# 1-Schematic_Power-vibrator_module.net
KiCad netlist of a schematic drawn in EasyEDA
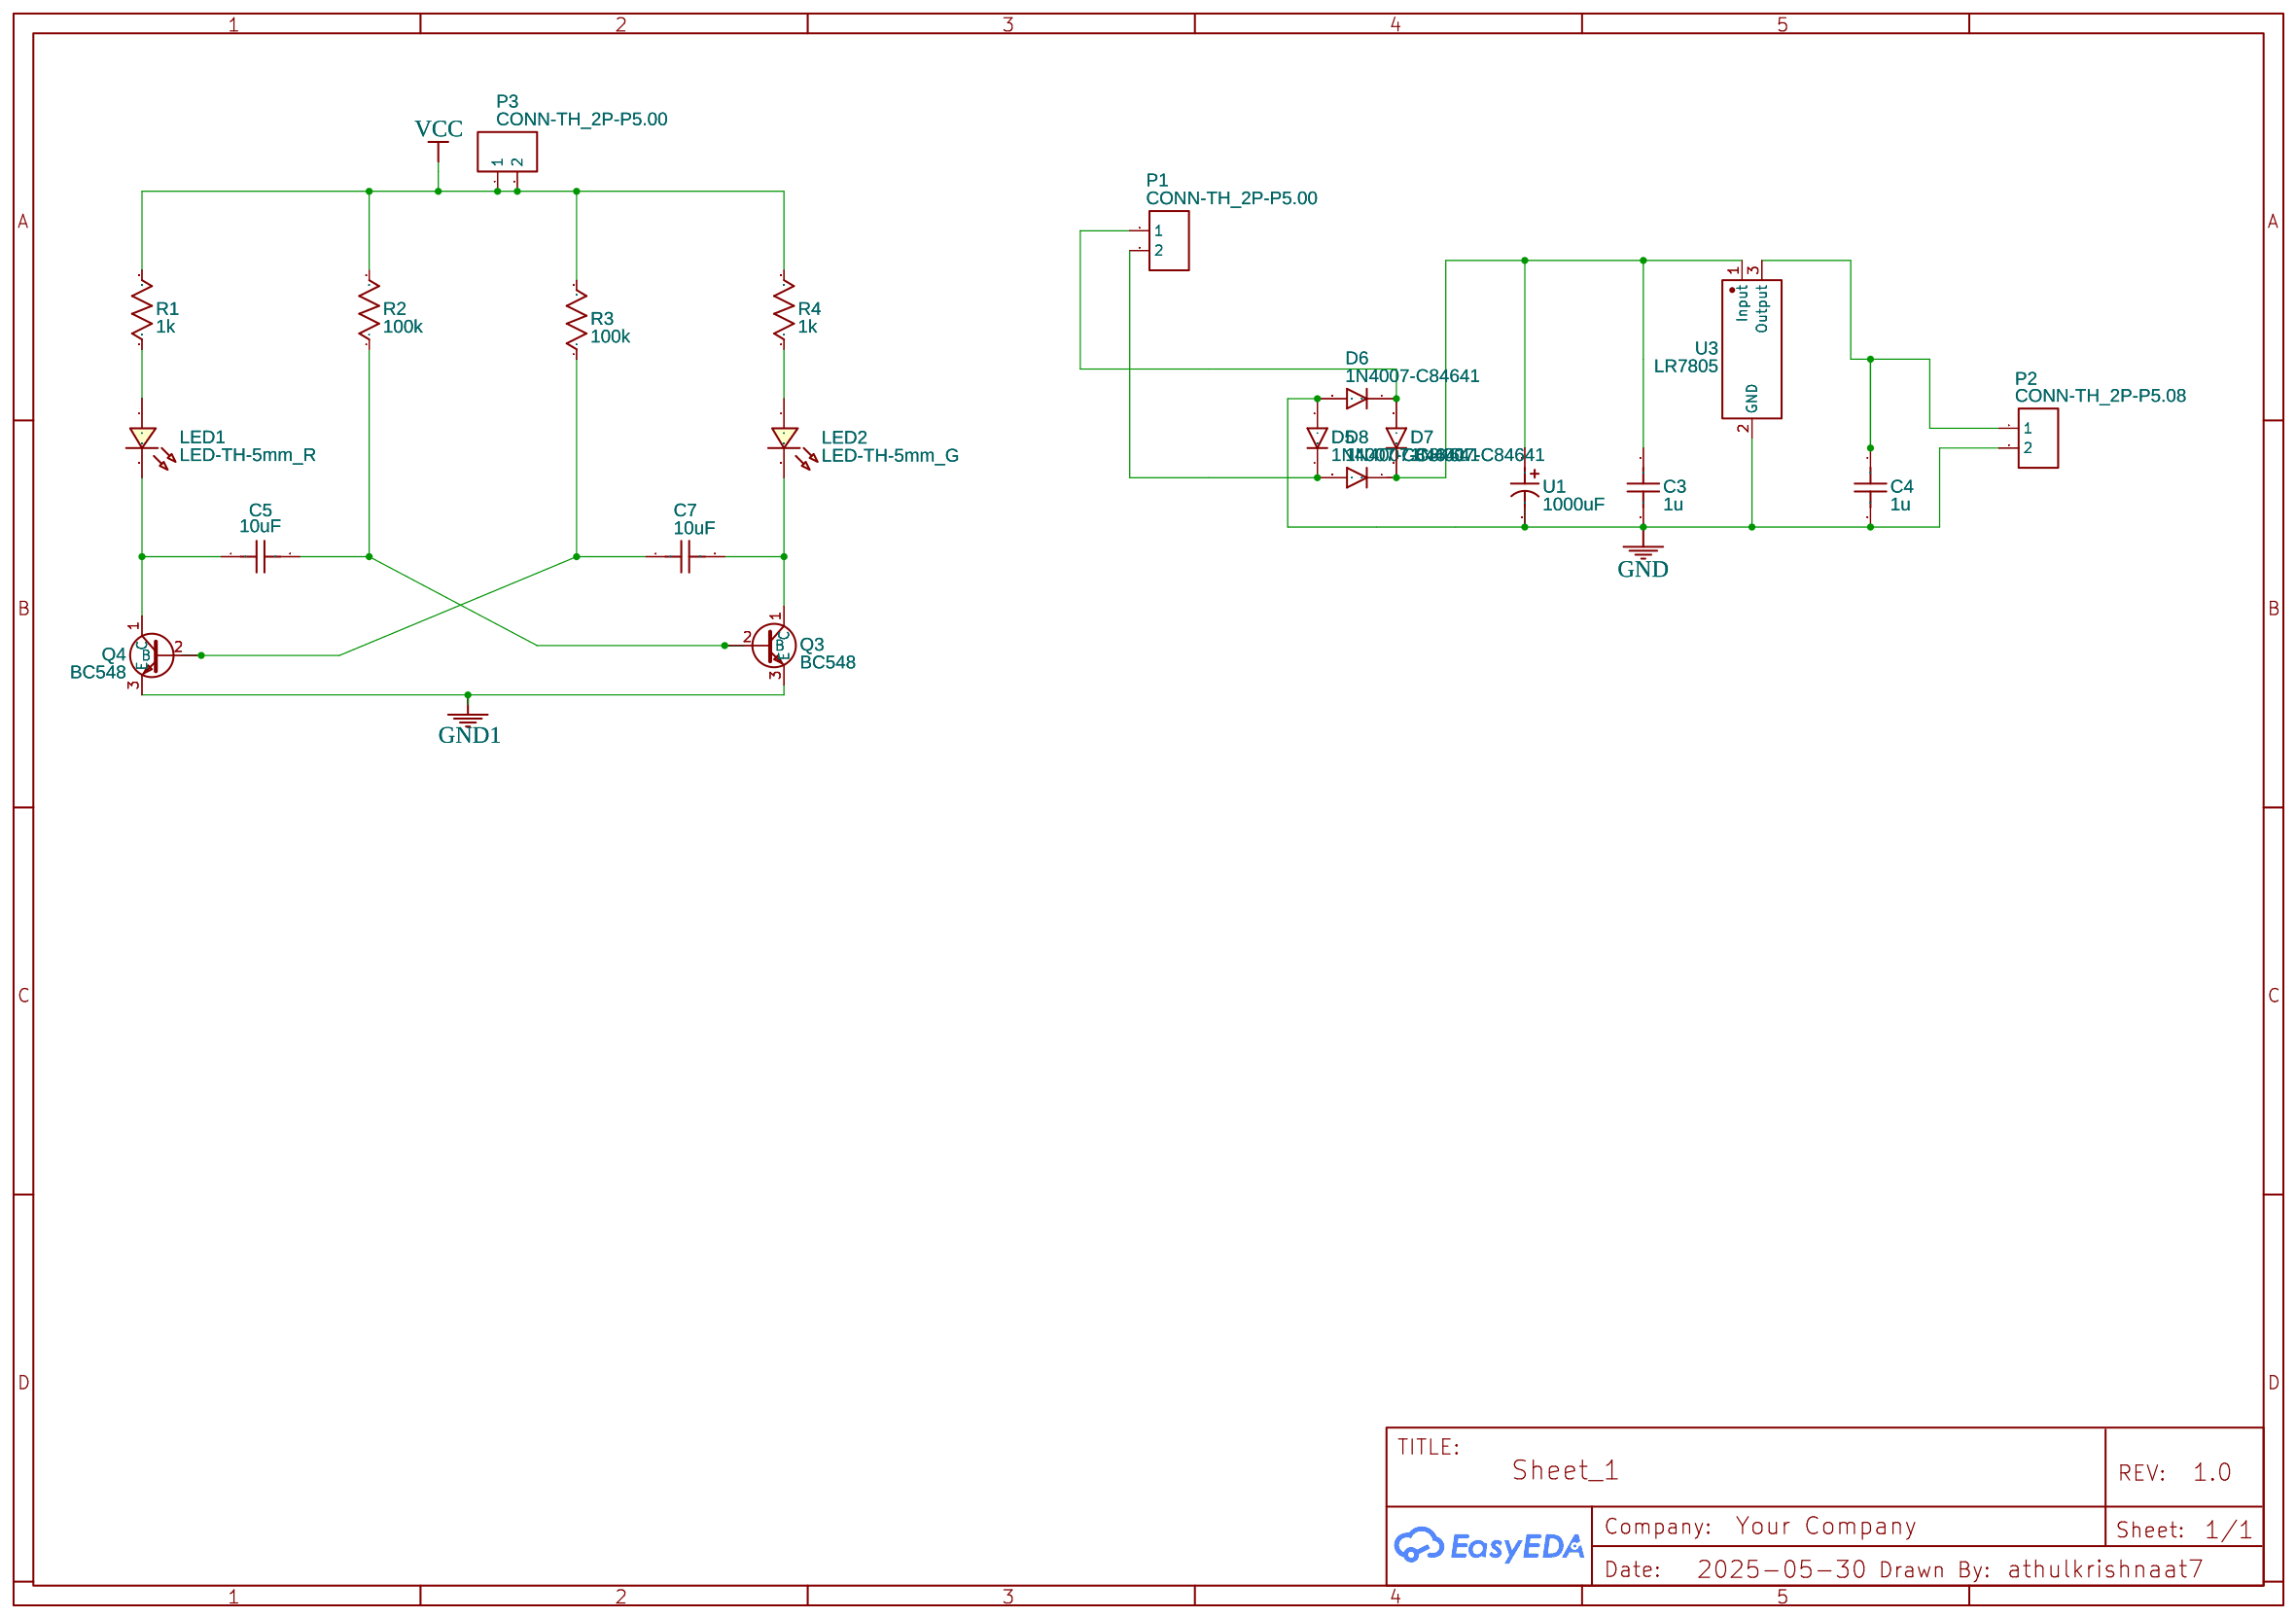
[diagram p0: schematic sheet]

(export (version "E")
  (design (tool "Eeschema 10.0.6"))
  (components
    (comp (ref "C3") (value "1u") (libsource (lib "") (part "C_RAD-0.1_US")))
    (comp (ref "C4") (value "1u") (libsource (lib "") (part "C_RAD-0.1_US")))
    (comp (ref "C5")
      (value "10uF")
      (fields (field (name "Manufacturer Part") "C324C106K3R5TA") (field (name "Manufacturer") "KEMET(基美)"))
      (libsource (lib "") (part "C324C106K3R5TA"))
    )
    (comp (ref "C7")
      (value "10uF")
      (fields (field (name "Manufacturer Part") "C324C106K3R5TA") (field (name "Manufacturer") "KEMET(基美)"))
      (libsource (lib "") (part "C324C106K3R5TA"))
    )
    (comp (ref "D5")
      (value "1N4007-C84641")
      (fields (field (name "Manufacturer Part") "1N4007") (field (name "Manufacturer") "星海"))
      (libsource (lib "") (part "1N4007-C84641_1"))
    )
    (comp (ref "D6")
      (value "1N4007-C84641")
      (fields (field (name "Manufacturer Part") "1N4007") (field (name "Manufacturer") "星海"))
      (libsource (lib "") (part "1N4007-C84641"))
    )
    (comp (ref "D7")
      (value "1N4007-C84641")
      (fields (field (name "Manufacturer Part") "1N4007") (field (name "Manufacturer") "星海"))
      (libsource (lib "") (part "1N4007-C84641_1"))
    )
    (comp (ref "D8")
      (value "1N4007-C84641")
      (fields (field (name "Manufacturer Part") "1N4007") (field (name "Manufacturer") "星海"))
      (libsource (lib "") (part "1N4007-C84641"))
    )
    (comp (ref "LED1")
      (value "LED-TH-5mm_R")
      (fields
        (field (name "Manufacturer Part") "333-2SURD/S530-A3")
        (field (name "Manufacturer") "EVERLIGHT(台湾亿光)")
      )
      (libsource (lib "") (part "LED-TH-5mm_R"))
    )
    (comp (ref "LED2")
      (value "LED-TH-5mm_G")
      (fields
        (field (name "Manufacturer Part") "333-2SYGD/S530-E2")
        (field (name "Manufacturer") "EVERLIGHT(台湾亿光)")
      )
      (libsource (lib "") (part "LED-TH-5mm_G"))
    )
    (comp (ref "P1") (value "CONN-TH_2P-P5.00") (libsource (lib "") (part "CONN-TH_2P-P5.00_1")))
    (comp (ref "P2") (value "CONN-TH_2P-P5.08") (libsource (lib "") (part "CONN-TH_2P-P5.08")))
    (comp (ref "P3") (value "CONN-TH_2P-P5.00") (libsource (lib "") (part "CONN-TH_2P-P5.00")))
    (comp (ref "Q3") (value "BC548") (libsource (lib "") (part "BC548_1")))
    (comp (ref "Q4") (value "BC548") (libsource (lib "") (part "BC548")))
    (comp (ref "R1") (value "1k") (libsource (lib "") (part "R_AXIAL-0.3_US")))
    (comp (ref "R2") (value "100k") (libsource (lib "") (part "R_AXIAL-0.3_US")))
    (comp (ref "R3") (value "100k") (libsource (lib "") (part "R_AXIAL-0.3_US")))
    (comp (ref "R4") (value "1k") (libsource (lib "") (part "R_AXIAL-0.3_US")))
    (comp (ref "U1")
      (value "1000uF")
      (fields
        (field (name "Manufacturer Part") "EGPA350ETD102MK25S")
        (field (name "Manufacturer") "NCC(日本贵弥功)")
      )
      (libsource (lib "") (part "EGPA350ETD102MK25S"))
    )
    (comp (ref "U3")
      (value "LR7805")
      (fields (field (name "Manufacturer") "LRC(乐山无线电)"))
      (libsource (lib "") (part "LR7805"))
    )
  )
  (nets
    (net (code "1") (name "GND") (class "Default")
      (node (ref "C3") (pin "2") (pinfunction "2_2") (pintype "unspecified"))
      (node (ref "C4") (pin "2") (pinfunction "2_2") (pintype "unspecified"))
      (node (ref "D5") (pin "2") (pinfunction "A_2") (pintype "unspecified"))
      (node (ref "D6") (pin "2") (pinfunction "A_2") (pintype "unspecified"))
      (node (ref "P2") (pin "2") (pinfunction "2_2") (pintype "unspecified"))
      (node (ref "U1") (pin "2") (pinfunction "2_2") (pintype "input"))
      (node (ref "U3") (pin "2") (pinfunction "GND_2") (pintype "unspecified"))
    )
    (net (code "2") (name "GND1") (class "Default")
      (node (ref "Q3") (pin "3") (pinfunction "E_3") (pintype "unspecified"))
      (node (ref "Q4") (pin "3") (pinfunction "E_3") (pintype "unspecified"))
    )
    (net (code "3") (name "Net-(D5-C)") (class "Default")
      (node (ref "D5") (pin "1") (pinfunction "C_1") (pintype "unspecified"))
      (node (ref "D8") (pin "2") (pinfunction "A_2") (pintype "unspecified"))
      (node (ref "P1") (pin "2") (pinfunction "2_2") (pintype "unspecified"))
    )
    (net (code "4") (name "Net-(D6-C)") (class "Default")
      (node (ref "D6") (pin "1") (pinfunction "C_1") (pintype "unspecified"))
      (node (ref "D7") (pin "2") (pinfunction "A_2") (pintype "unspecified"))
      (node (ref "P1") (pin "1") (pinfunction "1_1") (pintype "unspecified"))
    )
    (net (code "5") (name "Net-(D7-C)") (class "Default")
      (node (ref "C3") (pin "1") (pinfunction "1_1") (pintype "unspecified"))
      (node (ref "D7") (pin "1") (pinfunction "C_1") (pintype "unspecified"))
      (node (ref "D8") (pin "1") (pinfunction "C_1") (pintype "unspecified"))
      (node (ref "U1") (pin "1") (pinfunction "1_1") (pintype "input"))
      (node (ref "U3") (pin "1") (pinfunction "Input_1") (pintype "unspecified"))
    )
    (net (code "6") (name "Net-(LED1-Pad1)") (class "Default")
      (node (ref "LED1") (pin "1") (pinfunction "1_1") (pintype "unspecified"))
      (node (ref "R1") (pin "1") (pinfunction "1_1") (pintype "unspecified"))
    )
    (net (code "7") (name "Net-(LED2-Pad1)") (class "Default")
      (node (ref "LED2") (pin "1") (pinfunction "1_1") (pintype "unspecified"))
      (node (ref "R4") (pin "1") (pinfunction "1_1") (pintype "unspecified"))
    )
    (net (code "8") (name "Net-(Q3-B)") (class "Default")
      (node (ref "C5") (pin "2") (pinfunction "2_2") (pintype "unspecified"))
      (node (ref "Q3") (pin "2") (pinfunction "B_2") (pintype "input"))
      (node (ref "R2") (pin "1") (pinfunction "1_1") (pintype "unspecified"))
    )
    (net (code "9") (name "Net-(Q3-C)") (class "Default")
      (node (ref "C7") (pin "2") (pinfunction "2_2") (pintype "unspecified"))
      (node (ref "LED2") (pin "2") (pinfunction "2_2") (pintype "unspecified"))
      (node (ref "Q3") (pin "1") (pinfunction "C_1") (pintype "unspecified"))
    )
    (net (code "10") (name "Net-(Q4-B)") (class "Default")
      (node (ref "C7") (pin "1") (pinfunction "1_1") (pintype "unspecified"))
      (node (ref "Q4") (pin "2") (pinfunction "B_2") (pintype "input"))
      (node (ref "R3") (pin "1") (pinfunction "1_1") (pintype "unspecified"))
    )
    (net (code "11") (name "Net-(Q4-C)") (class "Default")
      (node (ref "C5") (pin "1") (pinfunction "1_1") (pintype "unspecified"))
      (node (ref "LED1") (pin "2") (pinfunction "2_2") (pintype "unspecified"))
      (node (ref "Q4") (pin "1") (pinfunction "C_1") (pintype "unspecified"))
    )
    (net (code "12") (name "Net-(U3-Output)") (class "Default")
      (node (ref "C4") (pin "1") (pinfunction "1_1") (pintype "unspecified"))
      (node (ref "P2") (pin "1") (pinfunction "1_1") (pintype "unspecified"))
      (node (ref "U3") (pin "3") (pinfunction "Output_3") (pintype "unspecified"))
    )
    (net (code "13") (name "VCC") (class "Default")
      (node (ref "P3") (pin "1") (pinfunction "1_1") (pintype "unspecified"))
      (node (ref "P3") (pin "2") (pinfunction "2_2") (pintype "unspecified"))
      (node (ref "R1") (pin "2") (pinfunction "2_2") (pintype "unspecified"))
      (node (ref "R2") (pin "2") (pinfunction "2_2") (pintype "unspecified"))
      (node (ref "R3") (pin "2") (pinfunction "2_2") (pintype "unspecified"))
      (node (ref "R4") (pin "2") (pinfunction "2_2") (pintype "unspecified"))
    )
  )
)
